# esp-n64.net
KiCad netlist of a schematic drawn in EAGLE
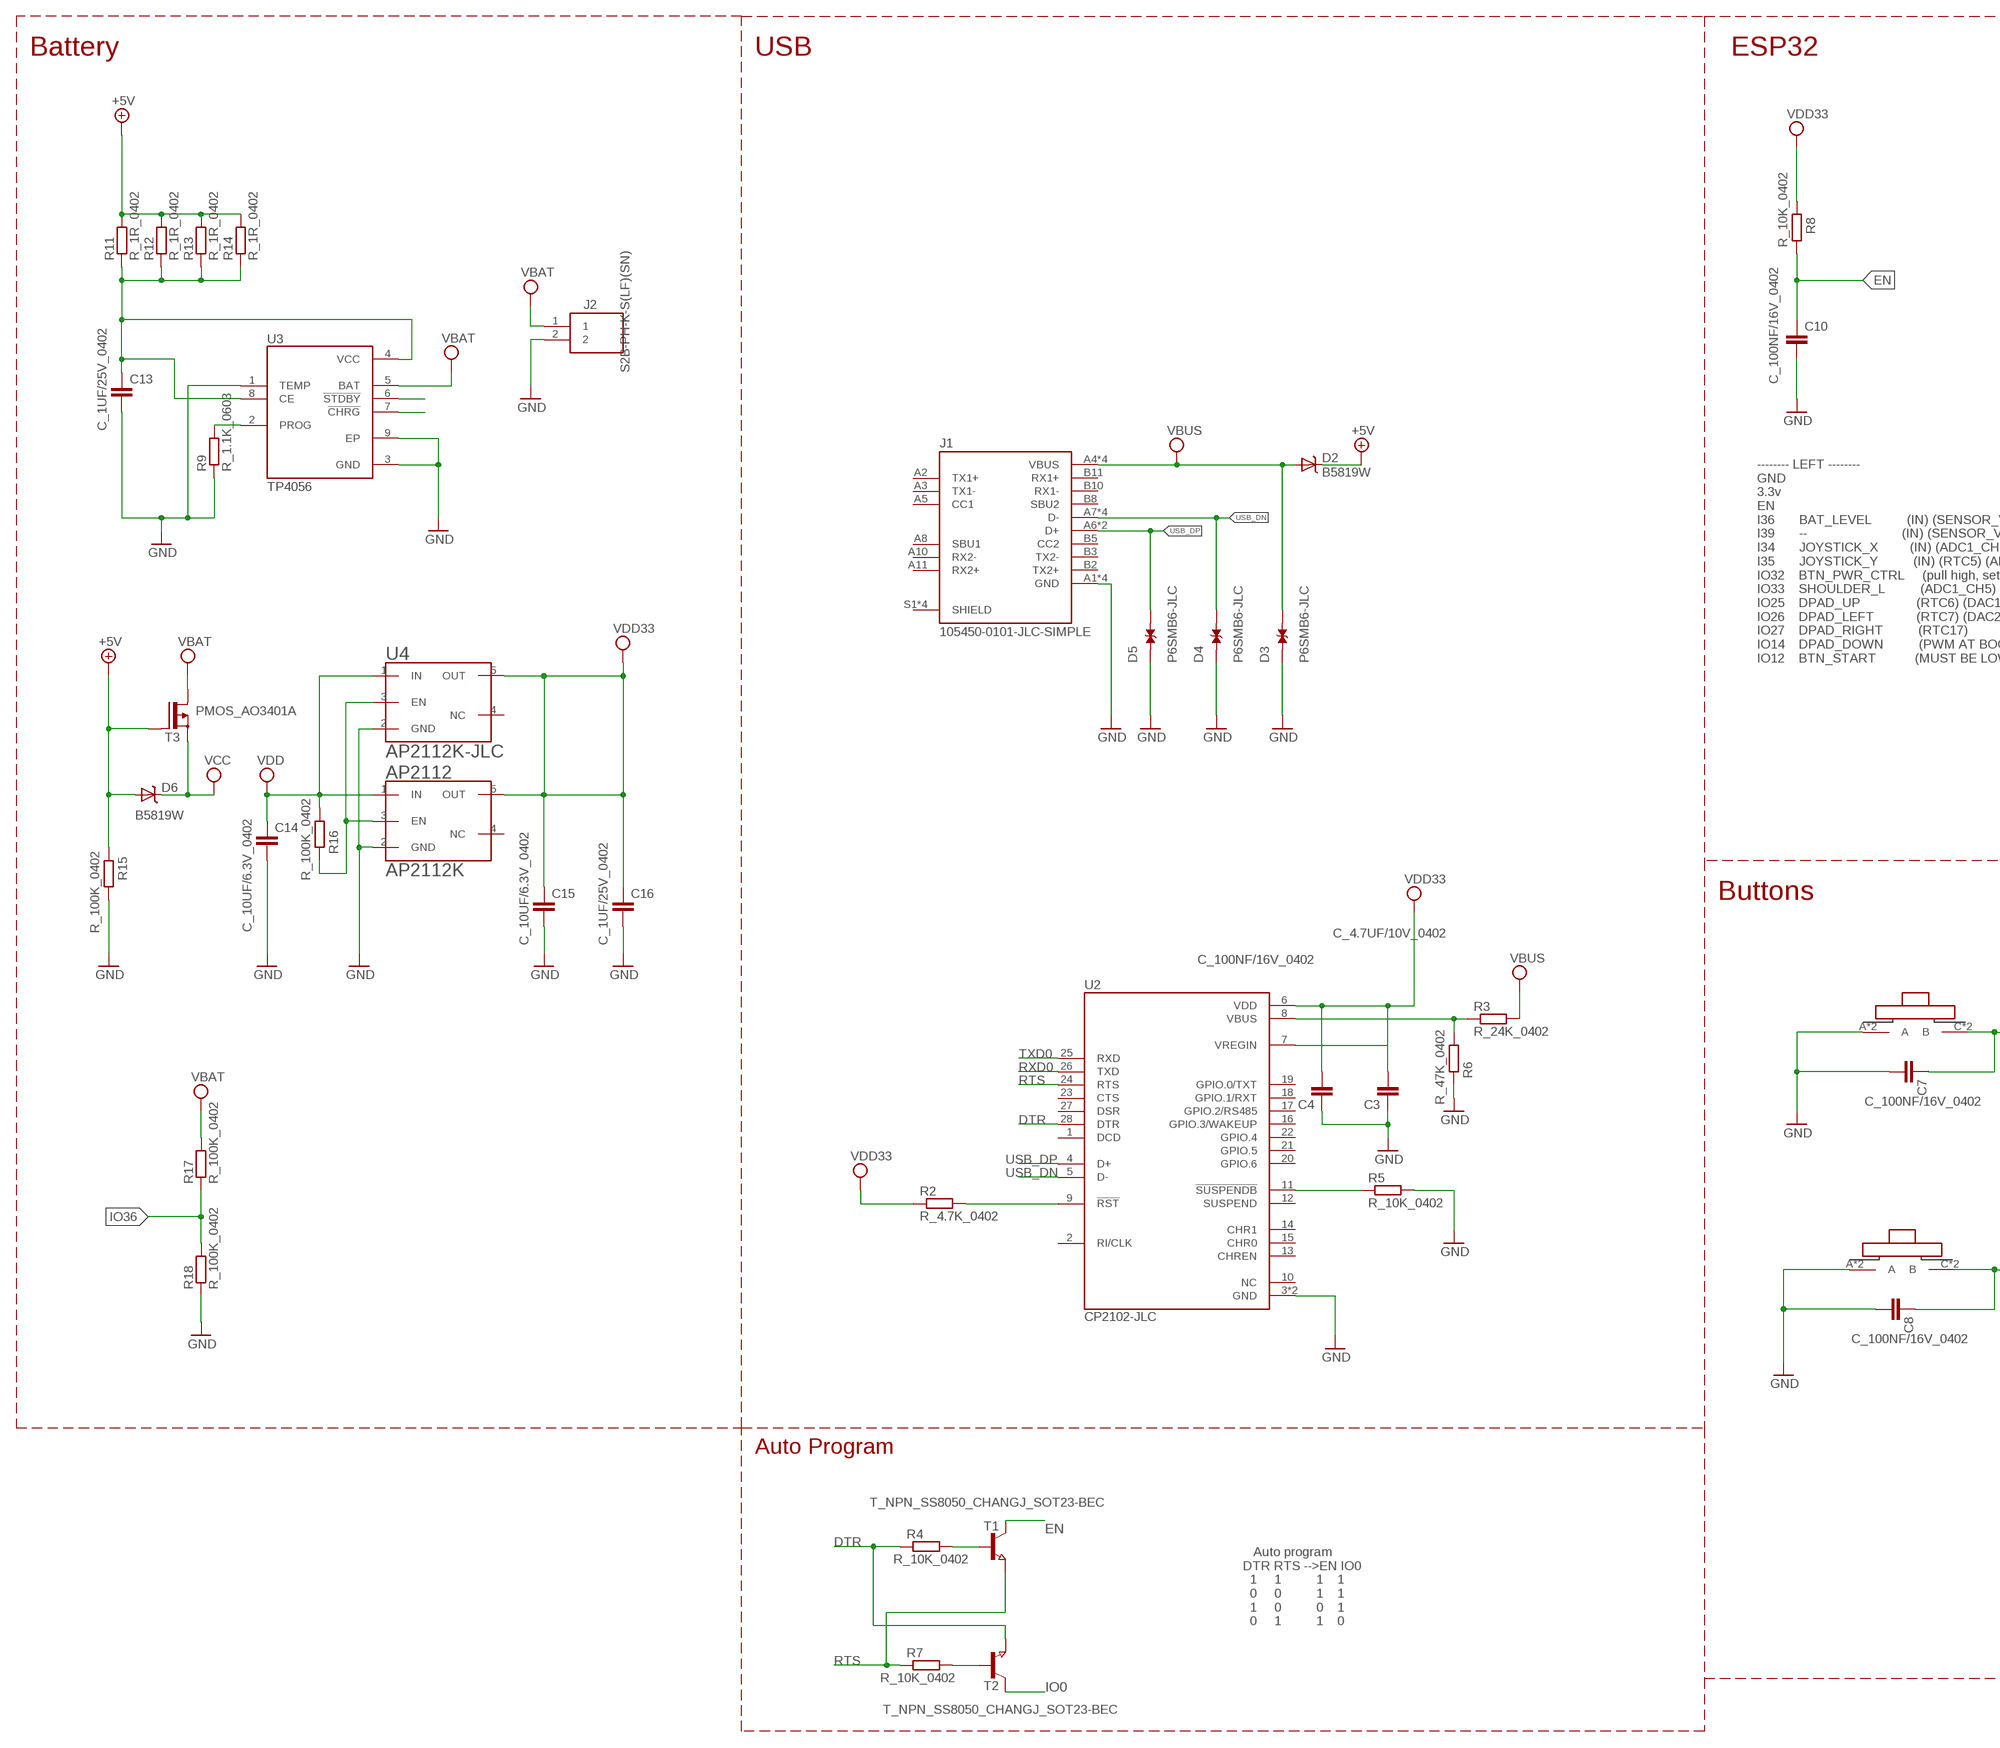
[diagram p0: schematic, sheet 1, part 1 of 2]
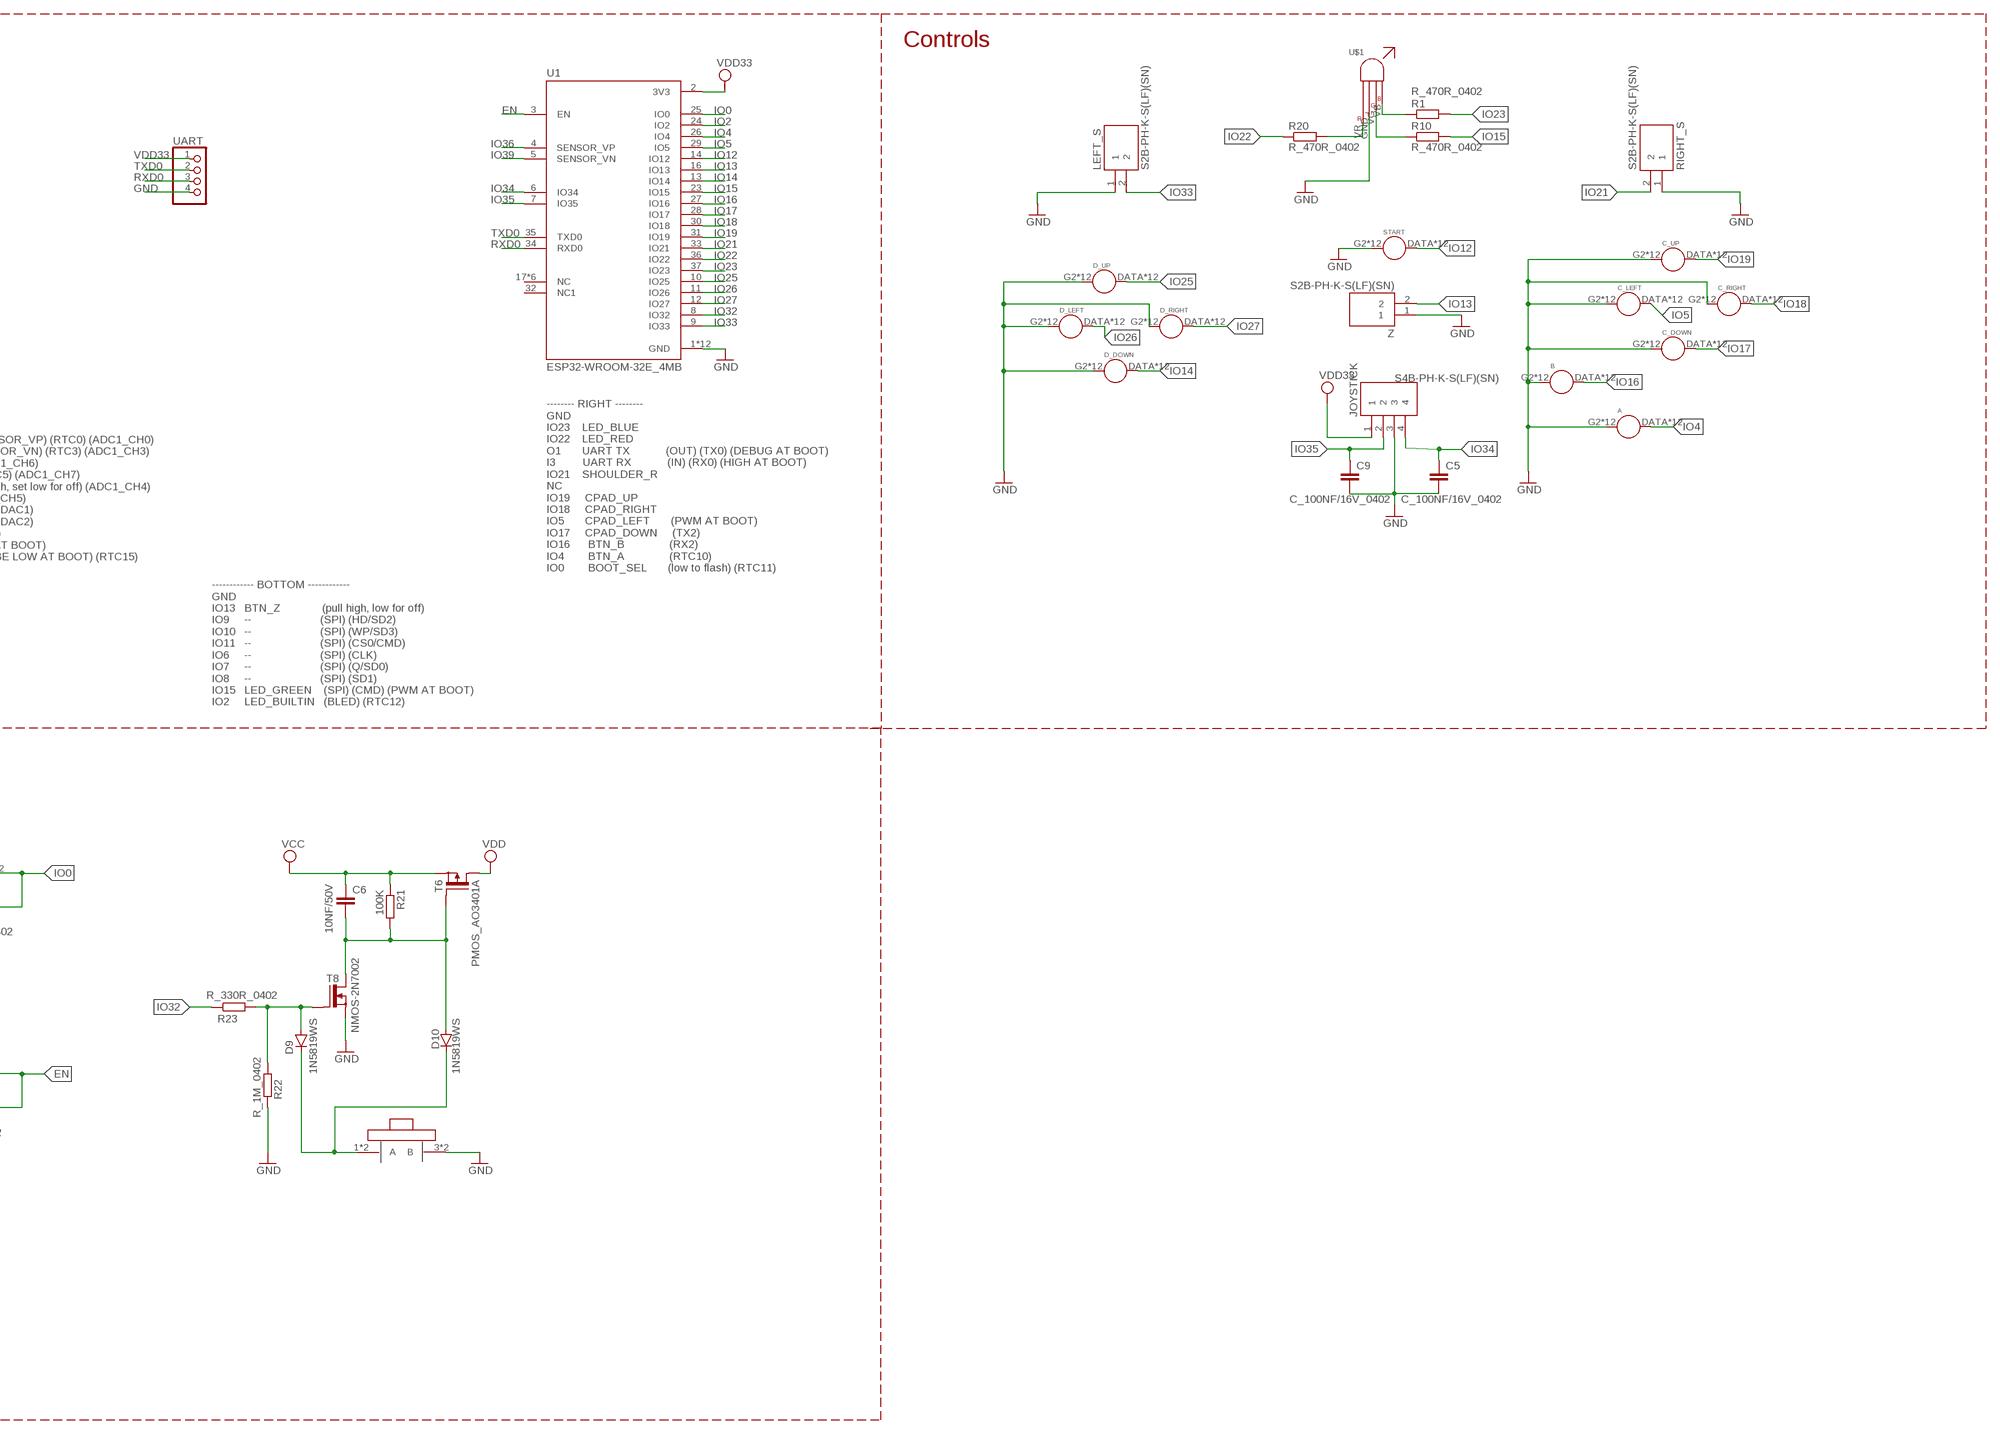
[diagram p1: schematic, sheet 1, part 2 of 2]

(export (version "E")
  (design (tool "Eeschema 10.0.6"))
  (components
    (comp (ref "A")
      (value "BUTTONPCB-CONDUCTIVE")
      (footprint "eagle-import:BUTTON-PAD")
      (libsource (lib "eagle-import") (part "BUTTONPCB-CONDUCTIVE"))
    )
    (comp (ref "AP2112")
      (value "AP2112K")
      (footprint "eagle-import:SOT-23-5")
      (libsource (lib "eagle-import") (part "AP2112K"))
    )
    (comp (ref "B")
      (value "BUTTONPCB-CONDUCTIVE")
      (footprint "eagle-import:BUTTON-PAD")
      (libsource (lib "eagle-import") (part "BUTTONPCB-CONDUCTIVE"))
    )
    (comp (ref "BOOT")
      (value "TS1187-SIMPLE")
      (footprint "eagle-import:TS1187")
      (fields (field (name "LCSC_PART") "C318884"))
      (libsource (lib "eagle-import") (part "TS1187-SIMPLE"))
    )
    (comp (ref "C3")
      (value "C_4.7UF/10V_0402")
      (footprint "eagle-import:C0402")
      (fields (field (name "LCSC_PART") "C23733"))
      (libsource (lib "eagle-import") (part "C__04024.7UF/10V"))
    )
    (comp (ref "C4")
      (value "C_100NF/16V_0402")
      (footprint "eagle-import:C0402")
      (fields (field (name "LCSC_PART") "C1525"))
      (libsource (lib "eagle-import") (part "C__0402100NF/16V"))
    )
    (comp (ref "C5")
      (value "C_100NF/16V_0402")
      (footprint "eagle-import:C0402")
      (fields (field (name "LCSC_PART") "C1525"))
      (libsource (lib "eagle-import") (part "C__0402100NF/16V"))
    )
    (comp (ref "C6")
      (value "10NF/50V")
      (footprint "eagle-import:C0402")
      (fields (field (name "LCSC_PART") "C15195"))
      (libsource (lib "eagle-import") (part "C__040210NF/50V"))
    )
    (comp (ref "C7")
      (value "C_100NF/16V_0402")
      (footprint "eagle-import:C0402")
      (fields (field (name "LCSC_PART") "C1525"))
      (libsource (lib "eagle-import") (part "C__0402100NF/16V"))
    )
    (comp (ref "C8")
      (value "C_100NF/16V_0402")
      (footprint "eagle-import:C0402")
      (fields (field (name "LCSC_PART") "C1525"))
      (libsource (lib "eagle-import") (part "C__0402100NF/16V"))
    )
    (comp (ref "C9")
      (value "C_100NF/16V_0402")
      (footprint "eagle-import:C0402")
      (fields (field (name "LCSC_PART") "C1525"))
      (libsource (lib "eagle-import") (part "C__0402100NF/16V"))
    )
    (comp (ref "C10")
      (value "C_100NF/16V_0402")
      (footprint "eagle-import:C0402")
      (fields (field (name "LCSC_PART") "C1525"))
      (libsource (lib "eagle-import") (part "C__0402100NF/16V"))
    )
    (comp (ref "C13")
      (value "C_1UF/25V_0402")
      (footprint "eagle-import:C0402")
      (fields (field (name "LCSC_PART") "C52923"))
      (libsource (lib "eagle-import") (part "C__04021UF/25V"))
    )
    (comp (ref "C14")
      (value "C_10UF/6.3V_0402")
      (footprint "eagle-import:C0402")
      (fields (field (name "LCSC_PART") "C15525"))
      (libsource (lib "eagle-import") (part "C__040210UF/6.3V"))
    )
    (comp (ref "C15")
      (value "C_10UF/6.3V_0402")
      (footprint "eagle-import:C0402")
      (fields (field (name "LCSC_PART") "C15525"))
      (libsource (lib "eagle-import") (part "C__040210UF/6.3V"))
    )
    (comp (ref "C16")
      (value "C_1UF/25V_0402")
      (footprint "eagle-import:C0402")
      (fields (field (name "LCSC_PART") "C52923"))
      (libsource (lib "eagle-import") (part "C__04021UF/25V"))
    )
    (comp (ref "CTRL")
      (value "FSM14J-SIMPLE")
      (footprint "eagle-import:SW_FSM14J")
      (libsource (lib "eagle-import") (part "FSM14J-SIMPLE"))
    )
    (comp (ref "C_DOWN")
      (value "BUTTONPCB-CONDUCTIVE")
      (footprint "eagle-import:BUTTON-PAD")
      (libsource (lib "eagle-import") (part "BUTTONPCB-CONDUCTIVE"))
    )
    (comp (ref "C_LEFT")
      (value "BUTTONPCB-CONDUCTIVE")
      (footprint "eagle-import:BUTTON-PAD")
      (libsource (lib "eagle-import") (part "BUTTONPCB-CONDUCTIVE"))
    )
    (comp (ref "C_RIGHT")
      (value "BUTTONPCB-CONDUCTIVE")
      (footprint "eagle-import:BUTTON-PAD")
      (libsource (lib "eagle-import") (part "BUTTONPCB-CONDUCTIVE"))
    )
    (comp (ref "C_UP")
      (value "BUTTONPCB-CONDUCTIVE")
      (footprint "eagle-import:BUTTON-PAD")
      (libsource (lib "eagle-import") (part "BUTTONPCB-CONDUCTIVE"))
    )
    (comp (ref "D2")
      (value "B5819W")
      (footprint "eagle-import:SOD-123")
      (fields (field (name "LCSC_PART") "C8598") (field (name "MF") "MDD"))
      (libsource (lib "eagle-import") (part "B5819W"))
    )
    (comp (ref "D3")
      (value "P6SMB6-JLC")
      (footprint "eagle-import:P6SMB6")
      (fields
        (field (name "LCSC_PART") "C78395")
        (field (name "MF") "Brightking Elec (TAIWAN)")
        (field (name "MP") "P6SMB6.8CA")
      )
      (libsource (lib "eagle-import") (part "P6SMB6-JLC"))
    )
    (comp (ref "D4")
      (value "P6SMB6-JLC")
      (footprint "eagle-import:P6SMB6")
      (fields
        (field (name "LCSC_PART") "C78395")
        (field (name "MF") "Brightking Elec (TAIWAN)")
        (field (name "MP") "P6SMB6.8CA")
      )
      (libsource (lib "eagle-import") (part "P6SMB6-JLC"))
    )
    (comp (ref "D5")
      (value "P6SMB6-JLC")
      (footprint "eagle-import:P6SMB6")
      (fields
        (field (name "LCSC_PART") "C78395")
        (field (name "MF") "Brightking Elec (TAIWAN)")
        (field (name "MP") "P6SMB6.8CA")
      )
      (libsource (lib "eagle-import") (part "P6SMB6-JLC"))
    )
    (comp (ref "D6")
      (value "B5819W")
      (footprint "eagle-import:SOD-123")
      (fields (field (name "LCSC_PART") "C8598") (field (name "MF") "MDD"))
      (libsource (lib "eagle-import") (part "B5819W"))
    )
    (comp (ref "D9")
      (value "1N5819WS")
      (footprint "eagle-import:SOD323")
      (fields (field (name "LCSC_PART") "C191023"))
      (libsource (lib "eagle-import") (part "D__SOD3231N5819WS_GUANGH"))
    )
    (comp (ref "D10")
      (value "1N5819WS")
      (footprint "eagle-import:SOD323")
      (fields (field (name "LCSC_PART") "C191023"))
      (libsource (lib "eagle-import") (part "D__SOD3231N5819WS_GUANGH"))
    )
    (comp (ref "D_DOWN")
      (value "BUTTONPCB-CONDUCTIVE")
      (footprint "eagle-import:BUTTON-PAD")
      (libsource (lib "eagle-import") (part "BUTTONPCB-CONDUCTIVE"))
    )
    (comp (ref "D_LEFT")
      (value "BUTTONPCB-CONDUCTIVE")
      (footprint "eagle-import:BUTTON-PAD")
      (libsource (lib "eagle-import") (part "BUTTONPCB-CONDUCTIVE"))
    )
    (comp (ref "D_RIGHT")
      (value "BUTTONPCB-CONDUCTIVE")
      (footprint "eagle-import:BUTTON-PAD")
      (libsource (lib "eagle-import") (part "BUTTONPCB-CONDUCTIVE"))
    )
    (comp (ref "D_UP")
      (value "D_UP")
      (footprint "eagle-import:BUTTON-PAD")
      (libsource (lib "eagle-import") (part "BUTTONPCB-CONDUCTIVE"))
    )
    (comp (ref "J1")
      (value "105450-0101-JLC-SIMPLE")
      (footprint "eagle-import:MOLEX_105450-0101-SIMPLE")
      (fields
        (field (name "LCSC_PART") "C134092")
        (field (name "MF") "Molex")
        (field (name "MP") "1054500101")
      )
      (libsource (lib "eagle-import") (part "105450-0101-JLC-SIMPLE"))
    )
    (comp (ref "J2")
      (value "S2B-PH-K-S(LF)(SN)")
      (footprint "eagle-import:JST_S2B-PH-K-S(LF)(SN)")
      (fields (field (name "MF") "JST Sales America Inc."))
      (libsource (lib "eagle-import") (part "S2B-PH-K-S(LF)(SN)"))
    )
    (comp (ref "JOYSTICK")
      (value "S4B-PH-K-S(LF)(SN)")
      (footprint "eagle-import:JST_S4B-PH-K-S(LF)(SN)")
      (fields (field (name "MF") "JST Sales"))
      (libsource (lib "eagle-import") (part "S4B-PH-K-S(LF)(SN)"))
    )
    (comp (ref "LEFT_S")
      (value "S2B-PH-K-S(LF)(SN)")
      (footprint "eagle-import:JST_S2B-PH-K-S(LF)(SN)")
      (fields (field (name "MF") "JST Sales America Inc."))
      (libsource (lib "eagle-import") (part "S2B-PH-K-S(LF)(SN)"))
    )
    (comp (ref "R1")
      (value "R_470R_0402")
      (footprint "eagle-import:R0402")
      (fields (field (name "LCSC_PART") "C25117"))
      (libsource (lib "eagle-import") (part "R__0402470R"))
    )
    (comp (ref "R2")
      (value "R_4.7K_0402")
      (footprint "eagle-import:R0402")
      (fields (field (name "LCSC_PART") "C25900"))
      (libsource (lib "eagle-import") (part "R__04024.7K"))
    )
    (comp (ref "R3")
      (value "R_24K_0402")
      (footprint "eagle-import:R0402")
      (fields (field (name "LCSC_PART") "C25769"))
      (libsource (lib "eagle-import") (part "R__040224K"))
    )
    (comp (ref "R4")
      (value "R_10K_0402")
      (footprint "eagle-import:R0402")
      (fields (field (name "LCSC_PART") "C25744"))
      (libsource (lib "eagle-import") (part "R__040210K"))
    )
    (comp (ref "R5")
      (value "R_10K_0402")
      (footprint "eagle-import:R0402")
      (fields (field (name "LCSC_PART") "C25744"))
      (libsource (lib "eagle-import") (part "R__040210K"))
    )
    (comp (ref "R6")
      (value "R_47K_0402")
      (footprint "eagle-import:R0402")
      (fields (field (name "LCSC_PART") "C25792"))
      (libsource (lib "eagle-import") (part "R__040247K"))
    )
    (comp (ref "R7")
      (value "R_10K_0402")
      (footprint "eagle-import:R0402")
      (fields (field (name "LCSC_PART") "C25744"))
      (libsource (lib "eagle-import") (part "R__040210K"))
    )
    (comp (ref "R8")
      (value "R_10K_0402")
      (footprint "eagle-import:R0402")
      (fields (field (name "LCSC_PART") "C25744"))
      (libsource (lib "eagle-import") (part "R__040210K"))
    )
    (comp (ref "R9")
      (value "R_1.1K_0603")
      (footprint "eagle-import:R0603")
      (fields (field (name "LCSC_PART") "C22764"))
      (libsource (lib "eagle-import") (part "R__06031.1K"))
    )
    (comp (ref "R10")
      (value "R_470R_0402")
      (footprint "eagle-import:R0402")
      (fields (field (name "LCSC_PART") "C25117"))
      (libsource (lib "eagle-import") (part "R__0402470R"))
    )
    (comp (ref "R11")
      (value "R_1R_0402")
      (footprint "eagle-import:R0402")
      (fields (field (name "LCSC_PART") "C25086"))
      (libsource (lib "eagle-import") (part "R__04021R"))
    )
    (comp (ref "R12")
      (value "R_1R_0402")
      (footprint "eagle-import:R0402")
      (fields (field (name "LCSC_PART") "C25086"))
      (libsource (lib "eagle-import") (part "R__04021R"))
    )
    (comp (ref "R13")
      (value "R_1R_0402")
      (footprint "eagle-import:R0402")
      (fields (field (name "LCSC_PART") "C25086"))
      (libsource (lib "eagle-import") (part "R__04021R"))
    )
    (comp (ref "R14")
      (value "R_1R_0402")
      (footprint "eagle-import:R0402")
      (fields (field (name "LCSC_PART") "C25086"))
      (libsource (lib "eagle-import") (part "R__04021R"))
    )
    (comp (ref "R15")
      (value "R_100K_0402")
      (footprint "eagle-import:R0402")
      (fields (field (name "LCSC_PART") "C25741"))
      (libsource (lib "eagle-import") (part "R__0402100K"))
    )
    (comp (ref "R16")
      (value "R_100K_0402")
      (footprint "eagle-import:R0402")
      (fields (field (name "LCSC_PART") "C25741"))
      (libsource (lib "eagle-import") (part "R__0402100K"))
    )
    (comp (ref "R17")
      (value "R_100K_0402")
      (footprint "eagle-import:R0402")
      (fields (field (name "LCSC_PART") "C25741"))
      (libsource (lib "eagle-import") (part "R__0402100K"))
    )
    (comp (ref "R18")
      (value "R_100K_0402")
      (footprint "eagle-import:R0402")
      (fields (field (name "LCSC_PART") "C25741"))
      (libsource (lib "eagle-import") (part "R__0402100K"))
    )
    (comp (ref "R20")
      (value "R_470R_0402")
      (footprint "eagle-import:R0402")
      (fields (field (name "LCSC_PART") "C25117"))
      (libsource (lib "eagle-import") (part "R__0402470R"))
    )
    (comp (ref "R21")
      (value "100K")
      (footprint "eagle-import:R0402")
      (fields (field (name "LCSC_PART") "C25741"))
      (libsource (lib "eagle-import") (part "R__0402100K"))
    )
    (comp (ref "R22")
      (value "R_1M_0402")
      (footprint "eagle-import:R0402")
      (fields (field (name "LCSC_PART") "C26083"))
      (libsource (lib "eagle-import") (part "R__04021M"))
    )
    (comp (ref "R23")
      (value "R_330R_0402")
      (footprint "eagle-import:R0402")
      (fields (field (name "LCSC_PART") "C25104"))
      (libsource (lib "eagle-import") (part "R__0402330R"))
    )
    (comp (ref "RESET")
      (value "TS1187-SIMPLE")
      (footprint "eagle-import:TS1187")
      (fields (field (name "LCSC_PART") "C318884"))
      (libsource (lib "eagle-import") (part "TS1187-SIMPLE"))
    )
    (comp (ref "RIGHT_S")
      (value "S2B-PH-K-S(LF)(SN)")
      (footprint "eagle-import:JST_S2B-PH-K-S(LF)(SN)")
      (fields (field (name "MF") "JST Sales America Inc."))
      (libsource (lib "eagle-import") (part "S2B-PH-K-S(LF)(SN)"))
    )
    (comp (ref "START")
      (value "BUTTONPCB-CONDUCTIVE")
      (footprint "eagle-import:BUTTON-PAD")
      (libsource (lib "eagle-import") (part "BUTTONPCB-CONDUCTIVE"))
    )
    (comp (ref "T1")
      (value "T_NPN_SS8050_CHANGJ_SOT23-BEC")
      (footprint "eagle-import:SOT23")
      (fields (field (name "LCSC_PART") "C2150"))
      (libsource (lib "eagle-import") (part "T_NPN__SOT23-BECSS8050_CHANGJ"))
    )
    (comp (ref "T2")
      (value "T_NPN_SS8050_CHANGJ_SOT23-BEC")
      (footprint "eagle-import:SOT23")
      (fields (field (name "LCSC_PART") "C2150"))
      (libsource (lib "eagle-import") (part "T_NPN__SOT23-BECSS8050_CHANGJ"))
    )
    (comp (ref "T3")
      (value "PMOS_AO3401A")
      (footprint "eagle-import:SOT23")
      (fields (field (name "LCSC_PART") "C15127"))
      (libsource (lib "eagle-import") (part "T_P-MOSFET__SOT23-GSDAO3401A_ALPHA"))
    )
    (comp (ref "T6")
      (value "PMOS_AO3401A")
      (footprint "eagle-import:SOT23")
      (fields (field (name "LCSC_PART") "C15127"))
      (libsource (lib "eagle-import") (part "T_P-MOSFET__SOT23-GSDAO3401A_ALPHA"))
    )
    (comp (ref "T8")
      (value "NMOS-2N7002")
      (footprint "eagle-import:SOT23")
      (fields (field (name "LCSC_PART") "C8545"))
      (libsource (lib "eagle-import") (part "T_N-MOSFET__SOT23-GSD2N7002_CHANGJ"))
    )
    (comp (ref "U$1")
      (value "RGB-LED")
      (footprint "eagle-import:1X04-LED-RGB")
      (libsource (lib "eagle-import") (part "RGB-LED"))
    )
    (comp (ref "U1")
      (value "ESP32-WROOM-32E_4MB")
      (footprint "eagle-import:ESP32-WROOM-32E")
      (fields
        (field (name "LCSC_PART") "C701341")
        (field (name "MF") "Espressif Systems")
        (field (name "MP") "ESP32-WROOM-32E")
      )
      (libsource (lib "eagle-import") (part "ESP32-WROOM-32E_4MB"))
    )
    (comp (ref "U2")
      (value "CP2102-JLC")
      (footprint "eagle-import:QFN50P500X500X80-29N")
      (fields
        (field (name "LCSC_PART") "C6568")
        (field (name "MF") "Silicon Labs")
        (field (name "MP") "CP2102-GMR")
      )
      (libsource (lib "eagle-import") (part "CP2102-JLC"))
    )
    (comp (ref "U3")
      (value "TP4056")
      (footprint "eagle-import:SOP127P600X175-9N")
      (fields (field (name "LCSC_PART") "C16581") (field (name "MF") "NanJing Top Power ASIC Corp."))
      (libsource (lib "eagle-import") (part "TP4056"))
    )
    (comp (ref "U4")
      (value "AP2112K-JLC")
      (footprint "eagle-import:SOT-23-5")
      (fields (field (name "LCSC_PART") "C51118"))
      (libsource (lib "eagle-import") (part "AP2112K-JLC"))
    )
    (comp (ref "UART")
      (value "PINHD-1X4")
      (footprint "eagle-import:1X04")
      (libsource (lib "eagle-import") (part "PINHD-1X4"))
    )
    (comp (ref "Z")
      (value "S2B-PH-K-S(LF)(SN)")
      (footprint "eagle-import:JST_S2B-PH-K-S(LF)(SN)")
      (fields (field (name "MF") "JST Sales America Inc."))
      (libsource (lib "eagle-import") (part "S2B-PH-K-S(LF)(SN)"))
    )
  )
  (nets
    (net (code "1") (name "+5V") (class "Default")
      (node (ref "D2") (pin "C") (pinfunction "C_C") (pintype "passive"))
      (node (ref "D6") (pin "A") (pinfunction "A_A") (pintype "passive"))
      (node (ref "R11") (pin "2") (pinfunction "2_2") (pintype "passive"))
      (node (ref "R12") (pin "2") (pinfunction "2_2") (pintype "passive"))
      (node (ref "R13") (pin "2") (pinfunction "2_2") (pintype "passive"))
      (node (ref "R14") (pin "2") (pinfunction "2_2") (pintype "passive"))
      (node (ref "R15") (pin "2") (pinfunction "2_2") (pintype "passive"))
      (node (ref "T3") (pin "1") (pinfunction "G_1") (pintype "passive"))
    )
    (net (code "2") (name "/DTR") (class "Default")
      (node (ref "R4") (pin "1") (pinfunction "1_1") (pintype "passive"))
      (node (ref "T2") (pin "2") (pinfunction "E_2") (pintype "passive"))
      (node (ref "U2") (pin "28") (pinfunction "DTR_28") (pintype "output"))
    )
    (net (code "3") (name "/IO2") (class "Default")
      (node (ref "U1") (pin "24") (pinfunction "IO2_24") (pintype "bidirectional"))
    )
    (net (code "4") (name "/IO39") (class "Default")
      (node (ref "U1") (pin "5") (pinfunction "SENSOR_VN_5") (pintype "input"))
    )
    (net (code "5") (name "/RTS") (class "Default")
      (node (ref "R7") (pin "1") (pinfunction "1_1") (pintype "passive"))
      (node (ref "T1") (pin "2") (pinfunction "E_2") (pintype "passive"))
      (node (ref "U2") (pin "24") (pinfunction "RTS_24") (pintype "output"))
    )
    (net (code "6") (name "/RXD0") (class "Default")
      (node (ref "U1") (pin "34") (pinfunction "RXD0_34") (pintype "bidirectional"))
      (node (ref "U2") (pin "26") (pinfunction "TXD_26") (pintype "output"))
      (node (ref "UART") (pin "3") (pinfunction "3_3") (pintype "passive"))
    )
    (net (code "7") (name "/TXD0") (class "Default")
      (node (ref "U1") (pin "35") (pinfunction "TXD0_35") (pintype "bidirectional"))
      (node (ref "U2") (pin "25") (pinfunction "RXD_25") (pintype "input"))
      (node (ref "UART") (pin "2") (pinfunction "2_2") (pintype "passive"))
    )
    (net (code "8") (name "EN") (class "Default")
      (node (ref "C10") (pin "1") (pinfunction "1_1") (pintype "passive"))
      (node (ref "C8") (pin "1") (pinfunction "1_1") (pintype "passive"))
      (node (ref "R8") (pin "1") (pinfunction "1_1") (pintype "passive"))
      (node (ref "RESET") (pin "C") (pinfunction "B_C") (pintype "bidirectional"))
      (node (ref "RESET") (pin "D") (pinfunction "B_D") (pintype "bidirectional"))
      (node (ref "T1") (pin "3") (pinfunction "C_3") (pintype "passive"))
      (node (ref "U1") (pin "3") (pinfunction "EN_3") (pintype "input"))
    )
    (net (code "9") (name "GND") (class "Default")
      (node (ref "A") (pin "G10") (pinfunction "GND_G10") (pintype "power_in"))
      (node (ref "A") (pin "G11") (pinfunction "GND_G11") (pintype "power_in"))
      (node (ref "A") (pin "G12") (pinfunction "GND_G12") (pintype "power_in"))
      (node (ref "A") (pin "G2") (pinfunction "GND_G2") (pintype "power_in"))
      (node (ref "A") (pin "G3") (pinfunction "GND_G3") (pintype "power_in"))
      (node (ref "A") (pin "G4") (pinfunction "GND_G4") (pintype "power_in"))
      (node (ref "A") (pin "G5") (pinfunction "GND_G5") (pintype "power_in"))
      (node (ref "A") (pin "G6") (pinfunction "GND_G6") (pintype "power_in"))
      (node (ref "A") (pin "G7") (pinfunction "GND_G7") (pintype "power_in"))
      (node (ref "A") (pin "G8") (pinfunction "GND_G8") (pintype "power_in"))
      (node (ref "A") (pin "G9") (pinfunction "GND_G9") (pintype "power_in"))
      (node (ref "A") (pin "GND") (pinfunction "GND_GND") (pintype "power_in"))
      (node (ref "AP2112") (pin "2") (pinfunction "GND_2") (pintype "power_in"))
      (node (ref "B") (pin "G10") (pinfunction "GND_G10") (pintype "power_in"))
      (node (ref "B") (pin "G11") (pinfunction "GND_G11") (pintype "power_in"))
      (node (ref "B") (pin "G12") (pinfunction "GND_G12") (pintype "power_in"))
      (node (ref "B") (pin "G2") (pinfunction "GND_G2") (pintype "power_in"))
      (node (ref "B") (pin "G3") (pinfunction "GND_G3") (pintype "power_in"))
      (node (ref "B") (pin "G4") (pinfunction "GND_G4") (pintype "power_in"))
      (node (ref "B") (pin "G5") (pinfunction "GND_G5") (pintype "power_in"))
      (node (ref "B") (pin "G6") (pinfunction "GND_G6") (pintype "power_in"))
      (node (ref "B") (pin "G7") (pinfunction "GND_G7") (pintype "power_in"))
      (node (ref "B") (pin "G8") (pinfunction "GND_G8") (pintype "power_in"))
      (node (ref "B") (pin "G9") (pinfunction "GND_G9") (pintype "power_in"))
      (node (ref "B") (pin "GND") (pinfunction "GND_GND") (pintype "power_in"))
      (node (ref "BOOT") (pin "A") (pinfunction "A_A") (pintype "bidirectional"))
      (node (ref "BOOT") (pin "B") (pinfunction "A_B") (pintype "bidirectional"))
      (node (ref "C10") (pin "2") (pinfunction "2_2") (pintype "passive"))
      (node (ref "C13") (pin "2") (pinfunction "2_2") (pintype "passive"))
      (node (ref "C14") (pin "2") (pinfunction "2_2") (pintype "passive"))
      (node (ref "C15") (pin "2") (pinfunction "2_2") (pintype "passive"))
      (node (ref "C16") (pin "2") (pinfunction "2_2") (pintype "passive"))
      (node (ref "C3") (pin "1") (pinfunction "1_1") (pintype "passive"))
      (node (ref "C4") (pin "1") (pinfunction "1_1") (pintype "passive"))
      (node (ref "C5") (pin "2") (pinfunction "2_2") (pintype "passive"))
      (node (ref "C7") (pin "2") (pinfunction "2_2") (pintype "passive"))
      (node (ref "C8") (pin "2") (pinfunction "2_2") (pintype "passive"))
      (node (ref "C9") (pin "2") (pinfunction "2_2") (pintype "passive"))
      (node (ref "CTRL") (pin "3") (pinfunction "B_3") (pintype "bidirectional"))
      (node (ref "CTRL") (pin "4") (pinfunction "B_4") (pintype "bidirectional"))
      (node (ref "C_DOWN") (pin "G10") (pinfunction "GND_G10") (pintype "power_in"))
      (node (ref "C_DOWN") (pin "G11") (pinfunction "GND_G11") (pintype "power_in"))
      (node (ref "C_DOWN") (pin "G12") (pinfunction "GND_G12") (pintype "power_in"))
      (node (ref "C_DOWN") (pin "G2") (pinfunction "GND_G2") (pintype "power_in"))
      (node (ref "C_DOWN") (pin "G3") (pinfunction "GND_G3") (pintype "power_in"))
      (node (ref "C_DOWN") (pin "G4") (pinfunction "GND_G4") (pintype "power_in"))
      (node (ref "C_DOWN") (pin "G5") (pinfunction "GND_G5") (pintype "power_in"))
      (node (ref "C_DOWN") (pin "G6") (pinfunction "GND_G6") (pintype "power_in"))
      (node (ref "C_DOWN") (pin "G7") (pinfunction "GND_G7") (pintype "power_in"))
      (node (ref "C_DOWN") (pin "G8") (pinfunction "GND_G8") (pintype "power_in"))
      (node (ref "C_DOWN") (pin "G9") (pinfunction "GND_G9") (pintype "power_in"))
      (node (ref "C_DOWN") (pin "GND") (pinfunction "GND_GND") (pintype "power_in"))
      (node (ref "C_LEFT") (pin "G10") (pinfunction "GND_G10") (pintype "power_in"))
      (node (ref "C_LEFT") (pin "G11") (pinfunction "GND_G11") (pintype "power_in"))
      (node (ref "C_LEFT") (pin "G12") (pinfunction "GND_G12") (pintype "power_in"))
      (node (ref "C_LEFT") (pin "G2") (pinfunction "GND_G2") (pintype "power_in"))
      (node (ref "C_LEFT") (pin "G3") (pinfunction "GND_G3") (pintype "power_in"))
      (node (ref "C_LEFT") (pin "G4") (pinfunction "GND_G4") (pintype "power_in"))
      (node (ref "C_LEFT") (pin "G5") (pinfunction "GND_G5") (pintype "power_in"))
      (node (ref "C_LEFT") (pin "G6") (pinfunction "GND_G6") (pintype "power_in"))
      (node (ref "C_LEFT") (pin "G7") (pinfunction "GND_G7") (pintype "power_in"))
      (node (ref "C_LEFT") (pin "G8") (pinfunction "GND_G8") (pintype "power_in"))
      (node (ref "C_LEFT") (pin "G9") (pinfunction "GND_G9") (pintype "power_in"))
      (node (ref "C_LEFT") (pin "GND") (pinfunction "GND_GND") (pintype "power_in"))
      (node (ref "C_RIGHT") (pin "G10") (pinfunction "GND_G10") (pintype "power_in"))
      (node (ref "C_RIGHT") (pin "G11") (pinfunction "GND_G11") (pintype "power_in"))
      (node (ref "C_RIGHT") (pin "G12") (pinfunction "GND_G12") (pintype "power_in"))
      (node (ref "C_RIGHT") (pin "G2") (pinfunction "GND_G2") (pintype "power_in"))
      (node (ref "C_RIGHT") (pin "G3") (pinfunction "GND_G3") (pintype "power_in"))
      (node (ref "C_RIGHT") (pin "G4") (pinfunction "GND_G4") (pintype "power_in"))
      (node (ref "C_RIGHT") (pin "G5") (pinfunction "GND_G5") (pintype "power_in"))
      (node (ref "C_RIGHT") (pin "G6") (pinfunction "GND_G6") (pintype "power_in"))
      (node (ref "C_RIGHT") (pin "G7") (pinfunction "GND_G7") (pintype "power_in"))
      (node (ref "C_RIGHT") (pin "G8") (pinfunction "GND_G8") (pintype "power_in"))
      (node (ref "C_RIGHT") (pin "G9") (pinfunction "GND_G9") (pintype "power_in"))
      (node (ref "C_RIGHT") (pin "GND") (pinfunction "GND_GND") (pintype "power_in"))
      (node (ref "C_UP") (pin "G10") (pinfunction "GND_G10") (pintype "power_in"))
      (node (ref "C_UP") (pin "G11") (pinfunction "GND_G11") (pintype "power_in"))
      (node (ref "C_UP") (pin "G12") (pinfunction "GND_G12") (pintype "power_in"))
      (node (ref "C_UP") (pin "G2") (pinfunction "GND_G2") (pintype "power_in"))
      (node (ref "C_UP") (pin "G3") (pinfunction "GND_G3") (pintype "power_in"))
      (node (ref "C_UP") (pin "G4") (pinfunction "GND_G4") (pintype "power_in"))
      (node (ref "C_UP") (pin "G5") (pinfunction "GND_G5") (pintype "power_in"))
      (node (ref "C_UP") (pin "G6") (pinfunction "GND_G6") (pintype "power_in"))
      (node (ref "C_UP") (pin "G7") (pinfunction "GND_G7") (pintype "power_in"))
      (node (ref "C_UP") (pin "G8") (pinfunction "GND_G8") (pintype "power_in"))
      (node (ref "C_UP") (pin "G9") (pinfunction "GND_G9") (pintype "power_in"))
      (node (ref "C_UP") (pin "GND") (pinfunction "GND_GND") (pintype "power_in"))
      (node (ref "D3") (pin "1") (pinfunction "1_1") (pintype "passive"))
      (node (ref "D4") (pin "1") (pinfunction "1_1") (pintype "passive"))
      (node (ref "D5") (pin "1") (pinfunction "1_1") (pintype "passive"))
      (node (ref "D_DOWN") (pin "G10") (pinfunction "GND_G10") (pintype "power_in"))
      (node (ref "D_DOWN") (pin "G11") (pinfunction "GND_G11") (pintype "power_in"))
      (node (ref "D_DOWN") (pin "G12") (pinfunction "GND_G12") (pintype "power_in"))
      (node (ref "D_DOWN") (pin "G2") (pinfunction "GND_G2") (pintype "power_in"))
      (node (ref "D_DOWN") (pin "G3") (pinfunction "GND_G3") (pintype "power_in"))
      (node (ref "D_DOWN") (pin "G4") (pinfunction "GND_G4") (pintype "power_in"))
      (node (ref "D_DOWN") (pin "G5") (pinfunction "GND_G5") (pintype "power_in"))
      (node (ref "D_DOWN") (pin "G6") (pinfunction "GND_G6") (pintype "power_in"))
      (node (ref "D_DOWN") (pin "G7") (pinfunction "GND_G7") (pintype "power_in"))
      (node (ref "D_DOWN") (pin "G8") (pinfunction "GND_G8") (pintype "power_in"))
      (node (ref "D_DOWN") (pin "G9") (pinfunction "GND_G9") (pintype "power_in"))
      (node (ref "D_DOWN") (pin "GND") (pinfunction "GND_GND") (pintype "power_in"))
      (node (ref "D_LEFT") (pin "G10") (pinfunction "GND_G10") (pintype "power_in"))
      (node (ref "D_LEFT") (pin "G11") (pinfunction "GND_G11") (pintype "power_in"))
      (node (ref "D_LEFT") (pin "G12") (pinfunction "GND_G12") (pintype "power_in"))
      (node (ref "D_LEFT") (pin "G2") (pinfunction "GND_G2") (pintype "power_in"))
      (node (ref "D_LEFT") (pin "G3") (pinfunction "GND_G3") (pintype "power_in"))
      (node (ref "D_LEFT") (pin "G4") (pinfunction "GND_G4") (pintype "power_in"))
      (node (ref "D_LEFT") (pin "G5") (pinfunction "GND_G5") (pintype "power_in"))
      (node (ref "D_LEFT") (pin "G6") (pinfunction "GND_G6") (pintype "power_in"))
      (node (ref "D_LEFT") (pin "G7") (pinfunction "GND_G7") (pintype "power_in"))
      (node (ref "D_LEFT") (pin "G8") (pinfunction "GND_G8") (pintype "power_in"))
      (node (ref "D_LEFT") (pin "G9") (pinfunction "GND_G9") (pintype "power_in"))
      (node (ref "D_LEFT") (pin "GND") (pinfunction "GND_GND") (pintype "power_in"))
      (node (ref "D_RIGHT") (pin "G10") (pinfunction "GND_G10") (pintype "power_in"))
      (node (ref "D_RIGHT") (pin "G11") (pinfunction "GND_G11") (pintype "power_in"))
      (node (ref "D_RIGHT") (pin "G12") (pinfunction "GND_G12") (pintype "power_in"))
      (node (ref "D_RIGHT") (pin "G2") (pinfunction "GND_G2") (pintype "power_in"))
      (node (ref "D_RIGHT") (pin "G3") (pinfunction "GND_G3") (pintype "power_in"))
      (node (ref "D_RIGHT") (pin "G4") (pinfunction "GND_G4") (pintype "power_in"))
      (node (ref "D_RIGHT") (pin "G5") (pinfunction "GND_G5") (pintype "power_in"))
      (node (ref "D_RIGHT") (pin "G6") (pinfunction "GND_G6") (pintype "power_in"))
      (node (ref "D_RIGHT") (pin "G7") (pinfunction "GND_G7") (pintype "power_in"))
      (node (ref "D_RIGHT") (pin "G8") (pinfunction "GND_G8") (pintype "power_in"))
      (node (ref "D_RIGHT") (pin "G9") (pinfunction "GND_G9") (pintype "power_in"))
      (node (ref "D_RIGHT") (pin "GND") (pinfunction "GND_GND") (pintype "power_in"))
      (node (ref "D_UP") (pin "G10") (pinfunction "GND_G10") (pintype "power_in"))
      (node (ref "D_UP") (pin "G11") (pinfunction "GND_G11") (pintype "power_in"))
      (node (ref "D_UP") (pin "G12") (pinfunction "GND_G12") (pintype "power_in"))
      (node (ref "D_UP") (pin "G2") (pinfunction "GND_G2") (pintype "power_in"))
      (node (ref "D_UP") (pin "G3") (pinfunction "GND_G3") (pintype "power_in"))
      (node (ref "D_UP") (pin "G4") (pinfunction "GND_G4") (pintype "power_in"))
      (node (ref "D_UP") (pin "G5") (pinfunction "GND_G5") (pintype "power_in"))
      (node (ref "D_UP") (pin "G6") (pinfunction "GND_G6") (pintype "power_in"))
      (node (ref "D_UP") (pin "G7") (pinfunction "GND_G7") (pintype "power_in"))
      (node (ref "D_UP") (pin "G8") (pinfunction "GND_G8") (pintype "power_in"))
      (node (ref "D_UP") (pin "G9") (pinfunction "GND_G9") (pintype "power_in"))
      (node (ref "D_UP") (pin "GND") (pinfunction "GND_GND") (pintype "power_in"))
      (node (ref "J1") (pin "A1") (pinfunction "GND_A1") (pintype "power_in"))
      (node (ref "J1") (pin "A12") (pinfunction "GND_A12") (pintype "power_in"))
      (node (ref "J1") (pin "B1") (pinfunction "GND_B1") (pintype "power_in"))
      (node (ref "J1") (pin "B12") (pinfunction "GND_B12") (pintype "power_in"))
      (node (ref "J2") (pin "2") (pinfunction "2_2") (pintype "passive"))
      (node (ref "JOYSTICK") (pin "3") (pinfunction "3_3") (pintype "passive"))
      (node (ref "LEFT_S") (pin "1") (pinfunction "1_1") (pintype "passive"))
      (node (ref "R15") (pin "1") (pinfunction "1_1") (pintype "passive"))
      (node (ref "R18") (pin "1") (pinfunction "1_1") (pintype "passive"))
      (node (ref "R22") (pin "2") (pinfunction "2_2") (pintype "passive"))
      (node (ref "R5") (pin "2") (pinfunction "2_2") (pintype "passive"))
      (node (ref "R6") (pin "1") (pinfunction "1_1") (pintype "passive"))
      (node (ref "R9") (pin "1") (pinfunction "1_1") (pintype "passive"))
      (node (ref "RESET") (pin "A") (pinfunction "A_A") (pintype "bidirectional"))
      (node (ref "RESET") (pin "B") (pinfunction "A_B") (pintype "bidirectional"))
      (node (ref "RIGHT_S") (pin "1") (pinfunction "1_1") (pintype "passive"))
      (node (ref "START") (pin "G10") (pinfunction "GND_G10") (pintype "power_in"))
      (node (ref "START") (pin "G11") (pinfunction "GND_G11") (pintype "power_in"))
      (node (ref "START") (pin "G12") (pinfunction "GND_G12") (pintype "power_in"))
      (node (ref "START") (pin "G2") (pinfunction "GND_G2") (pintype "power_in"))
      (node (ref "START") (pin "G3") (pinfunction "GND_G3") (pintype "power_in"))
      (node (ref "START") (pin "G4") (pinfunction "GND_G4") (pintype "power_in"))
      (node (ref "START") (pin "G5") (pinfunction "GND_G5") (pintype "power_in"))
      (node (ref "START") (pin "G6") (pinfunction "GND_G6") (pintype "power_in"))
      (node (ref "START") (pin "G7") (pinfunction "GND_G7") (pintype "power_in"))
      (node (ref "START") (pin "G8") (pinfunction "GND_G8") (pintype "power_in"))
      (node (ref "START") (pin "G9") (pinfunction "GND_G9") (pintype "power_in"))
      (node (ref "START") (pin "GND") (pinfunction "GND_GND") (pintype "power_in"))
      (node (ref "T8") (pin "2") (pinfunction "S_2") (pintype "passive"))
      (node (ref "U$1") (pin "GND") (pinfunction "GND_GND") (pintype "power_in"))
      (node (ref "U1") (pin "1") (pinfunction "GND_1") (pintype "power_in"))
      (node (ref "U1") (pin "15") (pinfunction "GND_15") (pintype "power_in"))
      (node (ref "U1") (pin "38") (pinfunction "GND_38") (pintype "power_in"))
      (node (ref "U1") (pin "39_1") (pinfunction "GND_39_1") (pintype "power_in"))
      (node (ref "U1") (pin "39_2") (pinfunction "GND_39_2") (pintype "power_in"))
      (node (ref "U1") (pin "39_3") (pinfunction "GND_39_3") (pintype "power_in"))
      (node (ref "U1") (pin "39_4") (pinfunction "GND_39_4") (pintype "power_in"))
      (node (ref "U1") (pin "39_5") (pinfunction "GND_39_5") (pintype "power_in"))
      (node (ref "U1") (pin "39_6") (pinfunction "GND_39_6") (pintype "power_in"))
      (node (ref "U1") (pin "39_7") (pinfunction "GND_39_7") (pintype "power_in"))
      (node (ref "U1") (pin "39_8") (pinfunction "GND_39_8") (pintype "power_in"))
      (node (ref "U1") (pin "39_9") (pinfunction "GND_39_9") (pintype "power_in"))
      (node (ref "U2") (pin "29") (pinfunction "GND_29") (pintype "power_in"))
      (node (ref "U2") (pin "3") (pinfunction "GND_3") (pintype "power_in"))
      (node (ref "U3") (pin "1") (pinfunction "TEMP_1") (pintype "input"))
      (node (ref "U3") (pin "3") (pinfunction "GND_3") (pintype "power_in"))
      (node (ref "U3") (pin "9") (pinfunction "EP_9") (pintype "passive"))
      (node (ref "U4") (pin "2") (pinfunction "GND_2") (pintype "power_in"))
      (node (ref "UART") (pin "4") (pinfunction "4_4") (pintype "passive"))
      (node (ref "Z") (pin "1") (pinfunction "1_1") (pintype "passive"))
    )
    (net (code "10") (name "IO0") (class "Default")
      (node (ref "BOOT") (pin "C") (pinfunction "B_C") (pintype "bidirectional"))
      (node (ref "BOOT") (pin "D") (pinfunction "B_D") (pintype "bidirectional"))
      (node (ref "C7") (pin "1") (pinfunction "1_1") (pintype "passive"))
      (node (ref "T2") (pin "3") (pinfunction "C_3") (pintype "passive"))
      (node (ref "U1") (pin "25") (pinfunction "IO0_25") (pintype "bidirectional"))
    )
    (net (code "11") (name "IO4") (class "Default")
      (node (ref "A") (pin "DATA") (pinfunction "D_DATA") (pintype "bidirectional"))
      (node (ref "A") (pin "DATA10") (pinfunction "D_DATA10") (pintype "bidirectional"))
      (node (ref "A") (pin "DATA11") (pinfunction "D_DATA11") (pintype "bidirectional"))
      (node (ref "A") (pin "DATA12") (pinfunction "D_DATA12") (pintype "bidirectional"))
      (node (ref "A") (pin "DATA2") (pinfunction "D_DATA2") (pintype "bidirectional"))
      (node (ref "A") (pin "DATA3") (pinfunction "D_DATA3") (pintype "bidirectional"))
      (node (ref "A") (pin "DATA4") (pinfunction "D_DATA4") (pintype "bidirectional"))
      (node (ref "A") (pin "DATA5") (pinfunction "D_DATA5") (pintype "bidirectional"))
      (node (ref "A") (pin "DATA6") (pinfunction "D_DATA6") (pintype "bidirectional"))
      (node (ref "A") (pin "DATA7") (pinfunction "D_DATA7") (pintype "bidirectional"))
      (node (ref "A") (pin "DATA8") (pinfunction "D_DATA8") (pintype "bidirectional"))
      (node (ref "A") (pin "DATA9") (pinfunction "D_DATA9") (pintype "bidirectional"))
      (node (ref "U1") (pin "26") (pinfunction "IO4_26") (pintype "bidirectional"))
    )
    (net (code "12") (name "IO5") (class "Default")
      (node (ref "C_LEFT") (pin "DATA") (pinfunction "D_DATA") (pintype "bidirectional"))
      (node (ref "C_LEFT") (pin "DATA10") (pinfunction "D_DATA10") (pintype "bidirectional"))
      (node (ref "C_LEFT") (pin "DATA11") (pinfunction "D_DATA11") (pintype "bidirectional"))
      (node (ref "C_LEFT") (pin "DATA12") (pinfunction "D_DATA12") (pintype "bidirectional"))
      (node (ref "C_LEFT") (pin "DATA2") (pinfunction "D_DATA2") (pintype "bidirectional"))
      (node (ref "C_LEFT") (pin "DATA3") (pinfunction "D_DATA3") (pintype "bidirectional"))
      (node (ref "C_LEFT") (pin "DATA4") (pinfunction "D_DATA4") (pintype "bidirectional"))
      (node (ref "C_LEFT") (pin "DATA5") (pinfunction "D_DATA5") (pintype "bidirectional"))
      (node (ref "C_LEFT") (pin "DATA6") (pinfunction "D_DATA6") (pintype "bidirectional"))
      (node (ref "C_LEFT") (pin "DATA7") (pinfunction "D_DATA7") (pintype "bidirectional"))
      (node (ref "C_LEFT") (pin "DATA8") (pinfunction "D_DATA8") (pintype "bidirectional"))
      (node (ref "C_LEFT") (pin "DATA9") (pinfunction "D_DATA9") (pintype "bidirectional"))
      (node (ref "U1") (pin "29") (pinfunction "IO5_29") (pintype "bidirectional"))
    )
    (net (code "13") (name "IO12") (class "Default")
      (node (ref "START") (pin "DATA") (pinfunction "D_DATA") (pintype "bidirectional"))
      (node (ref "START") (pin "DATA10") (pinfunction "D_DATA10") (pintype "bidirectional"))
      (node (ref "START") (pin "DATA11") (pinfunction "D_DATA11") (pintype "bidirectional"))
      (node (ref "START") (pin "DATA12") (pinfunction "D_DATA12") (pintype "bidirectional"))
      (node (ref "START") (pin "DATA2") (pinfunction "D_DATA2") (pintype "bidirectional"))
      (node (ref "START") (pin "DATA3") (pinfunction "D_DATA3") (pintype "bidirectional"))
      (node (ref "START") (pin "DATA4") (pinfunction "D_DATA4") (pintype "bidirectional"))
      (node (ref "START") (pin "DATA5") (pinfunction "D_DATA5") (pintype "bidirectional"))
      (node (ref "START") (pin "DATA6") (pinfunction "D_DATA6") (pintype "bidirectional"))
      (node (ref "START") (pin "DATA7") (pinfunction "D_DATA7") (pintype "bidirectional"))
      (node (ref "START") (pin "DATA8") (pinfunction "D_DATA8") (pintype "bidirectional"))
      (node (ref "START") (pin "DATA9") (pinfunction "D_DATA9") (pintype "bidirectional"))
      (node (ref "U1") (pin "14") (pinfunction "IO12_14") (pintype "bidirectional"))
    )
    (net (code "14") (name "IO13") (class "Default")
      (node (ref "U1") (pin "16") (pinfunction "IO13_16") (pintype "bidirectional"))
      (node (ref "Z") (pin "2") (pinfunction "2_2") (pintype "passive"))
    )
    (net (code "15") (name "IO14") (class "Default")
      (node (ref "D_DOWN") (pin "DATA") (pinfunction "D_DATA") (pintype "bidirectional"))
      (node (ref "D_DOWN") (pin "DATA10") (pinfunction "D_DATA10") (pintype "bidirectional"))
      (node (ref "D_DOWN") (pin "DATA11") (pinfunction "D_DATA11") (pintype "bidirectional"))
      (node (ref "D_DOWN") (pin "DATA12") (pinfunction "D_DATA12") (pintype "bidirectional"))
      (node (ref "D_DOWN") (pin "DATA2") (pinfunction "D_DATA2") (pintype "bidirectional"))
      (node (ref "D_DOWN") (pin "DATA3") (pinfunction "D_DATA3") (pintype "bidirectional"))
      (node (ref "D_DOWN") (pin "DATA4") (pinfunction "D_DATA4") (pintype "bidirectional"))
      (node (ref "D_DOWN") (pin "DATA5") (pinfunction "D_DATA5") (pintype "bidirectional"))
      (node (ref "D_DOWN") (pin "DATA6") (pinfunction "D_DATA6") (pintype "bidirectional"))
      (node (ref "D_DOWN") (pin "DATA7") (pinfunction "D_DATA7") (pintype "bidirectional"))
      (node (ref "D_DOWN") (pin "DATA8") (pinfunction "D_DATA8") (pintype "bidirectional"))
      (node (ref "D_DOWN") (pin "DATA9") (pinfunction "D_DATA9") (pintype "bidirectional"))
      (node (ref "U1") (pin "13") (pinfunction "IO14_13") (pintype "bidirectional"))
    )
    (net (code "16") (name "IO15") (class "Default")
      (node (ref "R10") (pin "2") (pinfunction "2_2") (pintype "passive"))
      (node (ref "U1") (pin "23") (pinfunction "IO15_23") (pintype "bidirectional"))
    )
    (net (code "17") (name "IO16") (class "Default")
      (node (ref "B") (pin "DATA") (pinfunction "D_DATA") (pintype "bidirectional"))
      (node (ref "B") (pin "DATA10") (pinfunction "D_DATA10") (pintype "bidirectional"))
      (node (ref "B") (pin "DATA11") (pinfunction "D_DATA11") (pintype "bidirectional"))
      (node (ref "B") (pin "DATA12") (pinfunction "D_DATA12") (pintype "bidirectional"))
      (node (ref "B") (pin "DATA2") (pinfunction "D_DATA2") (pintype "bidirectional"))
      (node (ref "B") (pin "DATA3") (pinfunction "D_DATA3") (pintype "bidirectional"))
      (node (ref "B") (pin "DATA4") (pinfunction "D_DATA4") (pintype "bidirectional"))
      (node (ref "B") (pin "DATA5") (pinfunction "D_DATA5") (pintype "bidirectional"))
      (node (ref "B") (pin "DATA6") (pinfunction "D_DATA6") (pintype "bidirectional"))
      (node (ref "B") (pin "DATA7") (pinfunction "D_DATA7") (pintype "bidirectional"))
      (node (ref "B") (pin "DATA8") (pinfunction "D_DATA8") (pintype "bidirectional"))
      (node (ref "B") (pin "DATA9") (pinfunction "D_DATA9") (pintype "bidirectional"))
      (node (ref "U1") (pin "27") (pinfunction "IO16_27") (pintype "bidirectional"))
    )
    (net (code "18") (name "IO17") (class "Default")
      (node (ref "C_DOWN") (pin "DATA") (pinfunction "D_DATA") (pintype "bidirectional"))
      (node (ref "C_DOWN") (pin "DATA10") (pinfunction "D_DATA10") (pintype "bidirectional"))
      (node (ref "C_DOWN") (pin "DATA11") (pinfunction "D_DATA11") (pintype "bidirectional"))
      (node (ref "C_DOWN") (pin "DATA12") (pinfunction "D_DATA12") (pintype "bidirectional"))
      (node (ref "C_DOWN") (pin "DATA2") (pinfunction "D_DATA2") (pintype "bidirectional"))
      (node (ref "C_DOWN") (pin "DATA3") (pinfunction "D_DATA3") (pintype "bidirectional"))
      (node (ref "C_DOWN") (pin "DATA4") (pinfunction "D_DATA4") (pintype "bidirectional"))
      (node (ref "C_DOWN") (pin "DATA5") (pinfunction "D_DATA5") (pintype "bidirectional"))
      (node (ref "C_DOWN") (pin "DATA6") (pinfunction "D_DATA6") (pintype "bidirectional"))
      (node (ref "C_DOWN") (pin "DATA7") (pinfunction "D_DATA7") (pintype "bidirectional"))
      (node (ref "C_DOWN") (pin "DATA8") (pinfunction "D_DATA8") (pintype "bidirectional"))
      (node (ref "C_DOWN") (pin "DATA9") (pinfunction "D_DATA9") (pintype "bidirectional"))
      (node (ref "U1") (pin "28") (pinfunction "IO17_28") (pintype "bidirectional"))
    )
    (net (code "19") (name "IO18") (class "Default")
      (node (ref "C_RIGHT") (pin "DATA") (pinfunction "D_DATA") (pintype "bidirectional"))
      (node (ref "C_RIGHT") (pin "DATA10") (pinfunction "D_DATA10") (pintype "bidirectional"))
      (node (ref "C_RIGHT") (pin "DATA11") (pinfunction "D_DATA11") (pintype "bidirectional"))
      (node (ref "C_RIGHT") (pin "DATA12") (pinfunction "D_DATA12") (pintype "bidirectional"))
      (node (ref "C_RIGHT") (pin "DATA2") (pinfunction "D_DATA2") (pintype "bidirectional"))
      (node (ref "C_RIGHT") (pin "DATA3") (pinfunction "D_DATA3") (pintype "bidirectional"))
      (node (ref "C_RIGHT") (pin "DATA4") (pinfunction "D_DATA4") (pintype "bidirectional"))
      (node (ref "C_RIGHT") (pin "DATA5") (pinfunction "D_DATA5") (pintype "bidirectional"))
      (node (ref "C_RIGHT") (pin "DATA6") (pinfunction "D_DATA6") (pintype "bidirectional"))
      (node (ref "C_RIGHT") (pin "DATA7") (pinfunction "D_DATA7") (pintype "bidirectional"))
      (node (ref "C_RIGHT") (pin "DATA8") (pinfunction "D_DATA8") (pintype "bidirectional"))
      (node (ref "C_RIGHT") (pin "DATA9") (pinfunction "D_DATA9") (pintype "bidirectional"))
      (node (ref "U1") (pin "30") (pinfunction "IO18_30") (pintype "bidirectional"))
    )
    (net (code "20") (name "IO19") (class "Default")
      (node (ref "C_UP") (pin "DATA") (pinfunction "D_DATA") (pintype "bidirectional"))
      (node (ref "C_UP") (pin "DATA10") (pinfunction "D_DATA10") (pintype "bidirectional"))
      (node (ref "C_UP") (pin "DATA11") (pinfunction "D_DATA11") (pintype "bidirectional"))
      (node (ref "C_UP") (pin "DATA12") (pinfunction "D_DATA12") (pintype "bidirectional"))
      (node (ref "C_UP") (pin "DATA2") (pinfunction "D_DATA2") (pintype "bidirectional"))
      (node (ref "C_UP") (pin "DATA3") (pinfunction "D_DATA3") (pintype "bidirectional"))
      (node (ref "C_UP") (pin "DATA4") (pinfunction "D_DATA4") (pintype "bidirectional"))
      (node (ref "C_UP") (pin "DATA5") (pinfunction "D_DATA5") (pintype "bidirectional"))
      (node (ref "C_UP") (pin "DATA6") (pinfunction "D_DATA6") (pintype "bidirectional"))
      (node (ref "C_UP") (pin "DATA7") (pinfunction "D_DATA7") (pintype "bidirectional"))
      (node (ref "C_UP") (pin "DATA8") (pinfunction "D_DATA8") (pintype "bidirectional"))
      (node (ref "C_UP") (pin "DATA9") (pinfunction "D_DATA9") (pintype "bidirectional"))
      (node (ref "U1") (pin "31") (pinfunction "IO19_31") (pintype "bidirectional"))
    )
    (net (code "21") (name "IO21") (class "Default")
      (node (ref "RIGHT_S") (pin "2") (pinfunction "2_2") (pintype "passive"))
      (node (ref "U1") (pin "33") (pinfunction "IO21_33") (pintype "bidirectional"))
    )
    (net (code "22") (name "IO22") (class "Default")
      (node (ref "R20") (pin "1") (pinfunction "1_1") (pintype "passive"))
      (node (ref "U1") (pin "36") (pinfunction "IO22_36") (pintype "bidirectional"))
    )
    (net (code "23") (name "IO23") (class "Default")
      (node (ref "R1") (pin "2") (pinfunction "2_2") (pintype "passive"))
      (node (ref "U1") (pin "37") (pinfunction "IO23_37") (pintype "bidirectional"))
    )
    (net (code "24") (name "IO25") (class "Default")
      (node (ref "D_UP") (pin "DATA") (pinfunction "D_DATA") (pintype "bidirectional"))
      (node (ref "D_UP") (pin "DATA10") (pinfunction "D_DATA10") (pintype "bidirectional"))
      (node (ref "D_UP") (pin "DATA11") (pinfunction "D_DATA11") (pintype "bidirectional"))
      (node (ref "D_UP") (pin "DATA12") (pinfunction "D_DATA12") (pintype "bidirectional"))
      (node (ref "D_UP") (pin "DATA2") (pinfunction "D_DATA2") (pintype "bidirectional"))
      (node (ref "D_UP") (pin "DATA3") (pinfunction "D_DATA3") (pintype "bidirectional"))
      (node (ref "D_UP") (pin "DATA4") (pinfunction "D_DATA4") (pintype "bidirectional"))
      (node (ref "D_UP") (pin "DATA5") (pinfunction "D_DATA5") (pintype "bidirectional"))
      (node (ref "D_UP") (pin "DATA6") (pinfunction "D_DATA6") (pintype "bidirectional"))
      (node (ref "D_UP") (pin "DATA7") (pinfunction "D_DATA7") (pintype "bidirectional"))
      (node (ref "D_UP") (pin "DATA8") (pinfunction "D_DATA8") (pintype "bidirectional"))
      (node (ref "D_UP") (pin "DATA9") (pinfunction "D_DATA9") (pintype "bidirectional"))
      (node (ref "U1") (pin "10") (pinfunction "IO25_10") (pintype "bidirectional"))
    )
    (net (code "25") (name "IO26") (class "Default")
      (node (ref "D_LEFT") (pin "DATA") (pinfunction "D_DATA") (pintype "bidirectional"))
      (node (ref "D_LEFT") (pin "DATA10") (pinfunction "D_DATA10") (pintype "bidirectional"))
      (node (ref "D_LEFT") (pin "DATA11") (pinfunction "D_DATA11") (pintype "bidirectional"))
      (node (ref "D_LEFT") (pin "DATA12") (pinfunction "D_DATA12") (pintype "bidirectional"))
      (node (ref "D_LEFT") (pin "DATA2") (pinfunction "D_DATA2") (pintype "bidirectional"))
      (node (ref "D_LEFT") (pin "DATA3") (pinfunction "D_DATA3") (pintype "bidirectional"))
      (node (ref "D_LEFT") (pin "DATA4") (pinfunction "D_DATA4") (pintype "bidirectional"))
      (node (ref "D_LEFT") (pin "DATA5") (pinfunction "D_DATA5") (pintype "bidirectional"))
      (node (ref "D_LEFT") (pin "DATA6") (pinfunction "D_DATA6") (pintype "bidirectional"))
      (node (ref "D_LEFT") (pin "DATA7") (pinfunction "D_DATA7") (pintype "bidirectional"))
      (node (ref "D_LEFT") (pin "DATA8") (pinfunction "D_DATA8") (pintype "bidirectional"))
      (node (ref "D_LEFT") (pin "DATA9") (pinfunction "D_DATA9") (pintype "bidirectional"))
      (node (ref "U1") (pin "11") (pinfunction "IO26_11") (pintype "bidirectional"))
    )
    (net (code "26") (name "IO27") (class "Default")
      (node (ref "D_RIGHT") (pin "DATA") (pinfunction "D_DATA") (pintype "bidirectional"))
      (node (ref "D_RIGHT") (pin "DATA10") (pinfunction "D_DATA10") (pintype "bidirectional"))
      (node (ref "D_RIGHT") (pin "DATA11") (pinfunction "D_DATA11") (pintype "bidirectional"))
      (node (ref "D_RIGHT") (pin "DATA12") (pinfunction "D_DATA12") (pintype "bidirectional"))
      (node (ref "D_RIGHT") (pin "DATA2") (pinfunction "D_DATA2") (pintype "bidirectional"))
      (node (ref "D_RIGHT") (pin "DATA3") (pinfunction "D_DATA3") (pintype "bidirectional"))
      (node (ref "D_RIGHT") (pin "DATA4") (pinfunction "D_DATA4") (pintype "bidirectional"))
      (node (ref "D_RIGHT") (pin "DATA5") (pinfunction "D_DATA5") (pintype "bidirectional"))
      (node (ref "D_RIGHT") (pin "DATA6") (pinfunction "D_DATA6") (pintype "bidirectional"))
      (node (ref "D_RIGHT") (pin "DATA7") (pinfunction "D_DATA7") (pintype "bidirectional"))
      (node (ref "D_RIGHT") (pin "DATA8") (pinfunction "D_DATA8") (pintype "bidirectional"))
      (node (ref "D_RIGHT") (pin "DATA9") (pinfunction "D_DATA9") (pintype "bidirectional"))
      (node (ref "U1") (pin "12") (pinfunction "IO27_12") (pintype "bidirectional"))
    )
    (net (code "27") (name "IO32") (class "Default")
      (node (ref "R23") (pin "1") (pinfunction "1_1") (pintype "passive"))
      (node (ref "U1") (pin "8") (pinfunction "IO32_8") (pintype "bidirectional"))
    )
    (net (code "28") (name "IO33") (class "Default")
      (node (ref "LEFT_S") (pin "2") (pinfunction "2_2") (pintype "passive"))
      (node (ref "U1") (pin "9") (pinfunction "IO33_9") (pintype "bidirectional"))
    )
    (net (code "29") (name "IO34") (class "Default")
      (node (ref "C5") (pin "1") (pinfunction "1_1") (pintype "passive"))
      (node (ref "JOYSTICK") (pin "4") (pinfunction "4_4") (pintype "passive"))
      (node (ref "U1") (pin "6") (pinfunction "IO34_6") (pintype "input"))
    )
    (net (code "30") (name "IO35") (class "Default")
      (node (ref "C9") (pin "1") (pinfunction "1_1") (pintype "passive"))
      (node (ref "JOYSTICK") (pin "2") (pinfunction "2_2") (pintype "passive"))
      (node (ref "U1") (pin "7") (pinfunction "IO35_7") (pintype "input"))
    )
    (net (code "31") (name "IO36") (class "Default")
      (node (ref "R17") (pin "1") (pinfunction "1_1") (pintype "passive"))
      (node (ref "R18") (pin "2") (pinfunction "2_2") (pintype "passive"))
      (node (ref "U1") (pin "4") (pinfunction "SENSOR_VP_4") (pintype "input"))
    )
    (net (code "32") (name "Net-(AP2112-EN)") (class "Default")
      (node (ref "AP2112") (pin "3") (pinfunction "EN_3") (pintype "bidirectional"))
      (node (ref "R16") (pin "1") (pinfunction "1_1") (pintype "passive"))
      (node (ref "U4") (pin "3") (pinfunction "EN_3") (pintype "bidirectional"))
    )
    (net (code "33") (name "Net-(CTRL-A-Pad1)") (class "Default")
      (node (ref "CTRL") (pin "1") (pinfunction "A_1") (pintype "bidirectional"))
      (node (ref "CTRL") (pin "2") (pinfunction "A_2") (pintype "bidirectional"))
      (node (ref "D10") (pin "C") (pinfunction "C_C") (pintype "passive"))
      (node (ref "D9") (pin "C") (pinfunction "C_C") (pintype "passive"))
    )
    (net (code "34") (name "Net-(R1-Pad1)") (class "Default")
      (node (ref "R1") (pin "1") (pinfunction "1_1") (pintype "passive"))
      (node (ref "U$1") (pin "VB") (pinfunction "VB_VB") (pintype "bidirectional"))
    )
    (net (code "35") (name "Net-(R10-Pad1)") (class "Default")
      (node (ref "R10") (pin "1") (pinfunction "1_1") (pintype "passive"))
      (node (ref "U$1") (pin "VG") (pinfunction "VG_VG") (pintype "bidirectional"))
    )
    (net (code "36") (name "Net-(R20-Pad2)") (class "Default")
      (node (ref "R20") (pin "2") (pinfunction "2_2") (pintype "passive"))
      (node (ref "U$1") (pin "VR") (pinfunction "VR_VR") (pintype "bidirectional"))
    )
    (net (code "37") (name "Net-(T1-B)") (class "Default")
      (node (ref "R4") (pin "2") (pinfunction "2_2") (pintype "passive"))
      (node (ref "T1") (pin "1") (pinfunction "B_1") (pintype "passive"))
    )
    (net (code "38") (name "Net-(T2-B)") (class "Default")
      (node (ref "R7") (pin "2") (pinfunction "2_2") (pintype "passive"))
      (node (ref "T2") (pin "1") (pinfunction "B_1") (pintype "passive"))
    )
    (net (code "39") (name "Net-(T6-G)") (class "Default")
      (node (ref "C6") (pin "2") (pinfunction "2_2") (pintype "passive"))
      (node (ref "D10") (pin "A") (pinfunction "A_A") (pintype "passive"))
      (node (ref "R21") (pin "2") (pinfunction "2_2") (pintype "passive"))
      (node (ref "T6") (pin "1") (pinfunction "G_1") (pintype "passive"))
      (node (ref "T8") (pin "3") (pinfunction "D_3") (pintype "passive"))
    )
    (net (code "40") (name "Net-(T8-G)") (class "Default")
      (node (ref "D9") (pin "A") (pinfunction "A_A") (pintype "passive"))
      (node (ref "R22") (pin "1") (pinfunction "1_1") (pintype "passive"))
      (node (ref "R23") (pin "2") (pinfunction "2_2") (pintype "passive"))
      (node (ref "T8") (pin "1") (pinfunction "G_1") (pintype "passive"))
    )
    (net (code "41") (name "Net-(U2-VBUS)") (class "Default")
      (node (ref "R3") (pin "1") (pinfunction "1_1") (pintype "passive"))
      (node (ref "R6") (pin "2") (pinfunction "2_2") (pintype "passive"))
      (node (ref "U2") (pin "8") (pinfunction "VBUS_8") (pintype "power_in"))
    )
    (net (code "42") (name "Net-(U2-~{RST})") (class "Default")
      (node (ref "R2") (pin "2") (pinfunction "2_2") (pintype "passive"))
      (node (ref "U2") (pin "9") (pinfunction "~{RST}_9") (pintype "input"))
    )
    (net (code "43") (name "Net-(U2-~{SUSPENDB})") (class "Default")
      (node (ref "R5") (pin "1") (pinfunction "1_1") (pintype "passive"))
      (node (ref "U2") (pin "11") (pinfunction "~{SUSPENDB}_11") (pintype "output"))
    )
    (net (code "44") (name "Net-(U3-CE)") (class "Default")
      (node (ref "C13") (pin "1") (pinfunction "1_1") (pintype "passive"))
      (node (ref "R11") (pin "1") (pinfunction "1_1") (pintype "passive"))
      (node (ref "R12") (pin "1") (pinfunction "1_1") (pintype "passive"))
      (node (ref "R13") (pin "1") (pinfunction "1_1") (pintype "passive"))
      (node (ref "R14") (pin "1") (pinfunction "1_1") (pintype "passive"))
      (node (ref "U3") (pin "4") (pinfunction "VCC_4") (pintype "power_in"))
      (node (ref "U3") (pin "8") (pinfunction "CE_8") (pintype "input"))
    )
    (net (code "45") (name "Net-(U3-PROG)") (class "Default")
      (node (ref "R9") (pin "2") (pinfunction "2_2") (pintype "passive"))
      (node (ref "U3") (pin "2") (pinfunction "PROG_2") (pintype "bidirectional"))
    )
    (net (code "46") (name "USB_DN") (class "Default")
      (node (ref "D4") (pin "2") (pinfunction "2_2") (pintype "passive"))
      (node (ref "J1") (pin "A7") (pinfunction "D-_A7") (pintype "bidirectional"))
      (node (ref "J1") (pin "B7") (pinfunction "D-_B7") (pintype "bidirectional"))
      (node (ref "J1") (pin "P$1") (pinfunction "D-_P$1") (pintype "bidirectional"))
      (node (ref "J1") (pin "P$2") (pinfunction "D-_P$2") (pintype "bidirectional"))
      (node (ref "U2") (pin "5") (pinfunction "D-_5") (pintype "bidirectional"))
    )
    (net (code "47") (name "USB_DP") (class "Default")
      (node (ref "D5") (pin "2") (pinfunction "2_2") (pintype "passive"))
      (node (ref "J1") (pin "A6") (pinfunction "D+_A6") (pintype "bidirectional"))
      (node (ref "J1") (pin "B6") (pinfunction "D+_B6") (pintype "bidirectional"))
      (node (ref "U2") (pin "4") (pinfunction "D+_4") (pintype "bidirectional"))
    )
    (net (code "48") (name "VBAT") (class "Default")
      (node (ref "J2") (pin "1") (pinfunction "1_1") (pintype "passive"))
      (node (ref "R17") (pin "2") (pinfunction "2_2") (pintype "passive"))
      (node (ref "T3") (pin "3") (pinfunction "D_3") (pintype "passive"))
      (node (ref "U3") (pin "5") (pinfunction "BAT_5") (pintype "output"))
    )
    (net (code "49") (name "VBUS") (class "Default")
      (node (ref "D2") (pin "A") (pinfunction "A_A") (pintype "passive"))
      (node (ref "D3") (pin "2") (pinfunction "2_2") (pintype "passive"))
      (node (ref "J1") (pin "A4") (pinfunction "VBUS_A4") (pintype "power_in"))
      (node (ref "J1") (pin "A9") (pinfunction "VBUS_A9") (pintype "power_in"))
      (node (ref "J1") (pin "B4") (pinfunction "VBUS_B4") (pintype "power_in"))
      (node (ref "J1") (pin "B9") (pinfunction "VBUS_B9") (pintype "power_in"))
      (node (ref "R3") (pin "2") (pinfunction "2_2") (pintype "passive"))
    )
    (net (code "50") (name "VCC") (class "Default")
      (node (ref "C6") (pin "1") (pinfunction "1_1") (pintype "passive"))
      (node (ref "D6") (pin "C") (pinfunction "C_C") (pintype "passive"))
      (node (ref "R21") (pin "1") (pinfunction "1_1") (pintype "passive"))
      (node (ref "T3") (pin "2") (pinfunction "S_2") (pintype "passive"))
      (node (ref "T6") (pin "2") (pinfunction "S_2") (pintype "passive"))
    )
    (net (code "51") (name "VDD") (class "Default")
      (node (ref "AP2112") (pin "1") (pinfunction "IN_1") (pintype "input"))
      (node (ref "C14") (pin "1") (pinfunction "1_1") (pintype "passive"))
      (node (ref "R16") (pin "2") (pinfunction "2_2") (pintype "passive"))
      (node (ref "T6") (pin "3") (pinfunction "D_3") (pintype "passive"))
      (node (ref "U4") (pin "1") (pinfunction "IN_1") (pintype "input"))
    )
    (net (code "52") (name "VDD33") (class "Default")
      (node (ref "AP2112") (pin "5") (pinfunction "OUT_5") (pintype "power_in"))
      (node (ref "C15") (pin "1") (pinfunction "1_1") (pintype "passive"))
      (node (ref "C16") (pin "1") (pinfunction "1_1") (pintype "passive"))
      (node (ref "C3") (pin "2") (pinfunction "2_2") (pintype "passive"))
      (node (ref "C4") (pin "2") (pinfunction "2_2") (pintype "passive"))
      (node (ref "JOYSTICK") (pin "1") (pinfunction "1_1") (pintype "passive"))
      (node (ref "R2") (pin "1") (pinfunction "1_1") (pintype "passive"))
      (node (ref "R8") (pin "2") (pinfunction "2_2") (pintype "passive"))
      (node (ref "U1") (pin "2") (pinfunction "3V3_2") (pintype "power_in"))
      (node (ref "U2") (pin "6") (pinfunction "VDD_6") (pintype "power_in"))
      (node (ref "U2") (pin "7") (pinfunction "VREGIN_7") (pintype "power_in"))
      (node (ref "U4") (pin "5") (pinfunction "OUT_5") (pintype "power_in"))
      (node (ref "UART") (pin "1") (pinfunction "1_1") (pintype "passive"))
    )
    (net (code "53") (name "unconnected-(AP2112-NC-Pad4)") (class "Default")
      (node (ref "AP2112") (pin "4") (pinfunction "NC_4") (pintype "no_connect"))
    )
    (net (code "54") (name "unconnected-(J1-CC1-PadA5)") (class "Default")
      (node (ref "J1") (pin "A5") (pinfunction "CC1_A5") (pintype "no_connect"))
    )
    (net (code "55") (name "unconnected-(J1-CC2-PadB5)") (class "Default")
      (node (ref "J1") (pin "B5") (pinfunction "CC2_B5") (pintype "no_connect"))
    )
    (net (code "56") (name "unconnected-(J1-RX1+-PadB11)") (class "Default")
      (node (ref "J1") (pin "B11") (pinfunction "RX1+_B11") (pintype "no_connect"))
    )
    (net (code "57") (name "unconnected-(J1-RX1--PadB10)") (class "Default")
      (node (ref "J1") (pin "B10") (pinfunction "RX1-_B10") (pintype "no_connect"))
    )
    (net (code "58") (name "unconnected-(J1-RX2+-PadA11)") (class "Default")
      (node (ref "J1") (pin "A11") (pinfunction "RX2+_A11") (pintype "no_connect"))
    )
    (net (code "59") (name "unconnected-(J1-RX2--PadA10)") (class "Default")
      (node (ref "J1") (pin "A10") (pinfunction "RX2-_A10") (pintype "no_connect"))
    )
    (net (code "60") (name "unconnected-(J1-SBU1-PadA8)") (class "Default")
      (node (ref "J1") (pin "A8") (pinfunction "SBU1_A8") (pintype "no_connect"))
    )
    (net (code "61") (name "unconnected-(J1-SBU2-PadB8)") (class "Default")
      (node (ref "J1") (pin "B8") (pinfunction "SBU2_B8") (pintype "no_connect"))
    )
    (net (code "62") (name "unconnected-(J1-SHIELD-PadS1)") (class "Default")
      (node (ref "J1") (pin "S1") (pinfunction "SHIELD_S1") (pintype "no_connect"))
    )
    (net (code "63") (name "unconnected-(J1-SHIELD-PadS2)") (class "Default")
      (node (ref "J1") (pin "S2") (pinfunction "SHIELD_S2") (pintype "no_connect"))
    )
    (net (code "64") (name "unconnected-(J1-SHIELD-PadS3)") (class "Default")
      (node (ref "J1") (pin "S3") (pinfunction "SHIELD_S3") (pintype "no_connect"))
    )
    (net (code "65") (name "unconnected-(J1-SHIELD-PadS4)") (class "Default")
      (node (ref "J1") (pin "S4") (pinfunction "SHIELD_S4") (pintype "no_connect"))
    )
    (net (code "66") (name "unconnected-(J1-TX1+-PadA2)") (class "Default")
      (node (ref "J1") (pin "A2") (pinfunction "TX1+_A2") (pintype "no_connect"))
    )
    (net (code "67") (name "unconnected-(J1-TX1--PadA3)") (class "Default")
      (node (ref "J1") (pin "A3") (pinfunction "TX1-_A3") (pintype "no_connect"))
    )
    (net (code "68") (name "unconnected-(J1-TX2+-PadB2)") (class "Default")
      (node (ref "J1") (pin "B2") (pinfunction "TX2+_B2") (pintype "no_connect"))
    )
    (net (code "69") (name "unconnected-(J1-TX2--PadB3)") (class "Default")
      (node (ref "J1") (pin "B3") (pinfunction "TX2-_B3") (pintype "no_connect"))
    )
    (net (code "70") (name "unconnected-(U1-NC-Pad17)") (class "Default")
      (node (ref "U1") (pin "17") (pinfunction "NC_17") (pintype "no_connect"))
    )
    (net (code "71") (name "unconnected-(U1-NC-Pad18)") (class "Default")
      (node (ref "U1") (pin "18") (pinfunction "NC_18") (pintype "no_connect"))
    )
    (net (code "72") (name "unconnected-(U1-NC-Pad19)") (class "Default")
      (node (ref "U1") (pin "19") (pinfunction "NC_19") (pintype "no_connect"))
    )
    (net (code "73") (name "unconnected-(U1-NC-Pad20)") (class "Default")
      (node (ref "U1") (pin "20") (pinfunction "NC_20") (pintype "no_connect"))
    )
    (net (code "74") (name "unconnected-(U1-NC-Pad21)") (class "Default")
      (node (ref "U1") (pin "21") (pinfunction "NC_21") (pintype "no_connect"))
    )
    (net (code "75") (name "unconnected-(U1-NC-Pad22)") (class "Default")
      (node (ref "U1") (pin "22") (pinfunction "NC_22") (pintype "no_connect"))
    )
    (net (code "76") (name "unconnected-(U1-NC1-Pad32)") (class "Default")
      (node (ref "U1") (pin "32") (pinfunction "NC1_32") (pintype "no_connect"))
    )
    (net (code "77") (name "unconnected-(U2-CHR0-Pad15)") (class "Default")
      (node (ref "U2") (pin "15") (pinfunction "CHR0_15") (pintype "output"))
    )
    (net (code "78") (name "unconnected-(U2-CHR1-Pad14)") (class "Default")
      (node (ref "U2") (pin "14") (pinfunction "CHR1_14") (pintype "output"))
    )
    (net (code "79") (name "unconnected-(U2-CHREN-Pad13)") (class "Default")
      (node (ref "U2") (pin "13") (pinfunction "CHREN_13") (pintype "output"))
    )
    (net (code "80") (name "unconnected-(U2-CTS-Pad23)") (class "Default")
      (node (ref "U2") (pin "23") (pinfunction "CTS_23") (pintype "input"))
    )
    (net (code "81") (name "unconnected-(U2-DCD-Pad1)") (class "Default")
      (node (ref "U2") (pin "1") (pinfunction "DCD_1") (pintype "input"))
    )
    (net (code "82") (name "unconnected-(U2-DSR-Pad27)") (class "Default")
      (node (ref "U2") (pin "27") (pinfunction "DSR_27") (pintype "input"))
    )
    (net (code "83") (name "unconnected-(U2-GPIO.0{slash}TXT-Pad19)") (class "Default")
      (node (ref "U2") (pin "19") (pinfunction "GPIO.0/TXT_19") (pintype "bidirectional"))
    )
    (net (code "84") (name "unconnected-(U2-GPIO.1{slash}RXT-Pad18)") (class "Default")
      (node (ref "U2") (pin "18") (pinfunction "GPIO.1/RXT_18") (pintype "bidirectional"))
    )
    (net (code "85") (name "unconnected-(U2-GPIO.2{slash}RS485-Pad17)") (class "Default")
      (node (ref "U2") (pin "17") (pinfunction "GPIO.2/RS485_17") (pintype "bidirectional"))
    )
    (net (code "86") (name "unconnected-(U2-GPIO.3{slash}WAKEUP-Pad16)") (class "Default")
      (node (ref "U2") (pin "16") (pinfunction "GPIO.3/WAKEUP_16") (pintype "bidirectional"))
    )
    (net (code "87") (name "unconnected-(U2-GPIO.4-Pad22)") (class "Default")
      (node (ref "U2") (pin "22") (pinfunction "GPIO.4_22") (pintype "bidirectional"))
    )
    (net (code "88") (name "unconnected-(U2-GPIO.5-Pad21)") (class "Default")
      (node (ref "U2") (pin "21") (pinfunction "GPIO.5_21") (pintype "bidirectional"))
    )
    (net (code "89") (name "unconnected-(U2-GPIO.6-Pad20)") (class "Default")
      (node (ref "U2") (pin "20") (pinfunction "GPIO.6_20") (pintype "bidirectional"))
    )
    (net (code "90") (name "unconnected-(U2-NC-Pad10)") (class "Default")
      (node (ref "U2") (pin "10") (pinfunction "NC_10") (pintype "no_connect"))
    )
    (net (code "91") (name "unconnected-(U2-RI{slash}CLK-Pad2)") (class "Default")
      (node (ref "U2") (pin "2") (pinfunction "RI/CLK_2") (pintype "bidirectional"))
    )
    (net (code "92") (name "unconnected-(U2-SUSPEND-Pad12)") (class "Default")
      (node (ref "U2") (pin "12") (pinfunction "SUSPEND_12") (pintype "output"))
    )
    (net (code "93") (name "unconnected-(U3-~{CHRG}-Pad7)") (class "Default")
      (node (ref "U3") (pin "7") (pinfunction "~{CHRG}_7") (pintype "output"))
    )
    (net (code "94") (name "unconnected-(U3-~{STDBY}-Pad6)") (class "Default")
      (node (ref "U3") (pin "6") (pinfunction "~{STDBY}_6") (pintype "output"))
    )
    (net (code "95") (name "unconnected-(U4-NC-Pad4)") (class "Default")
      (node (ref "U4") (pin "4") (pinfunction "NC_4") (pintype "no_connect"))
    )
  )
)
